# v1.net
KiCad netlist of a schematic drawn in EAGLE
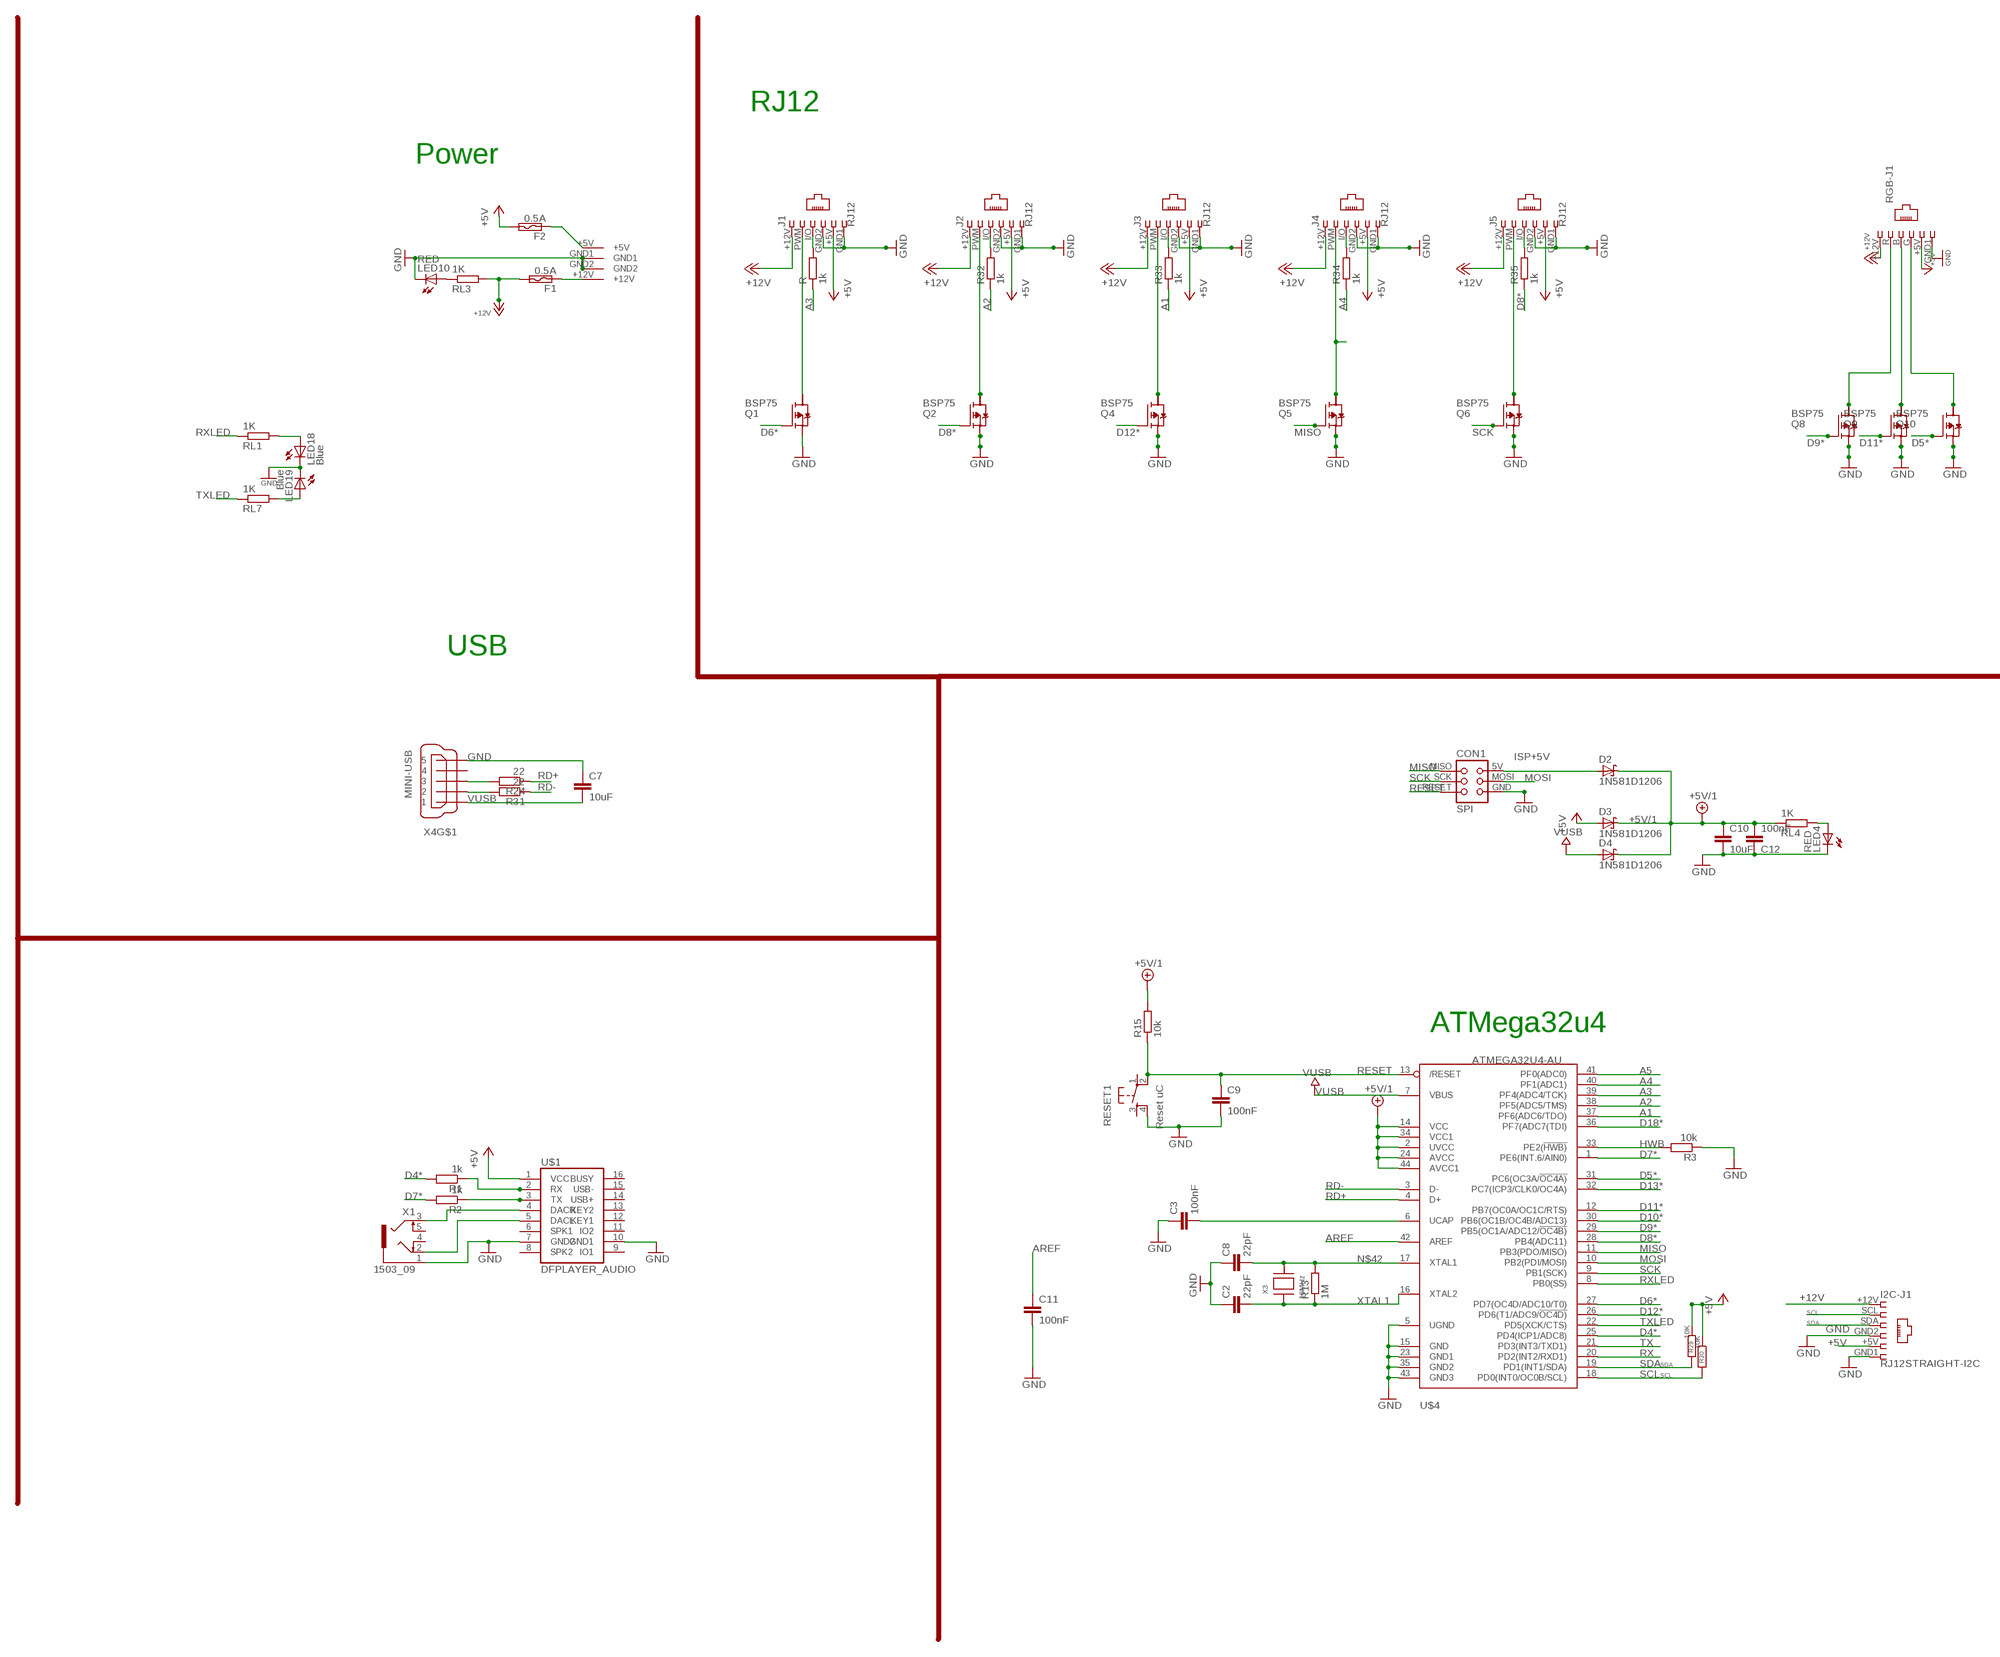
[diagram p0: schematic, sheet 1, part 1 of 2]
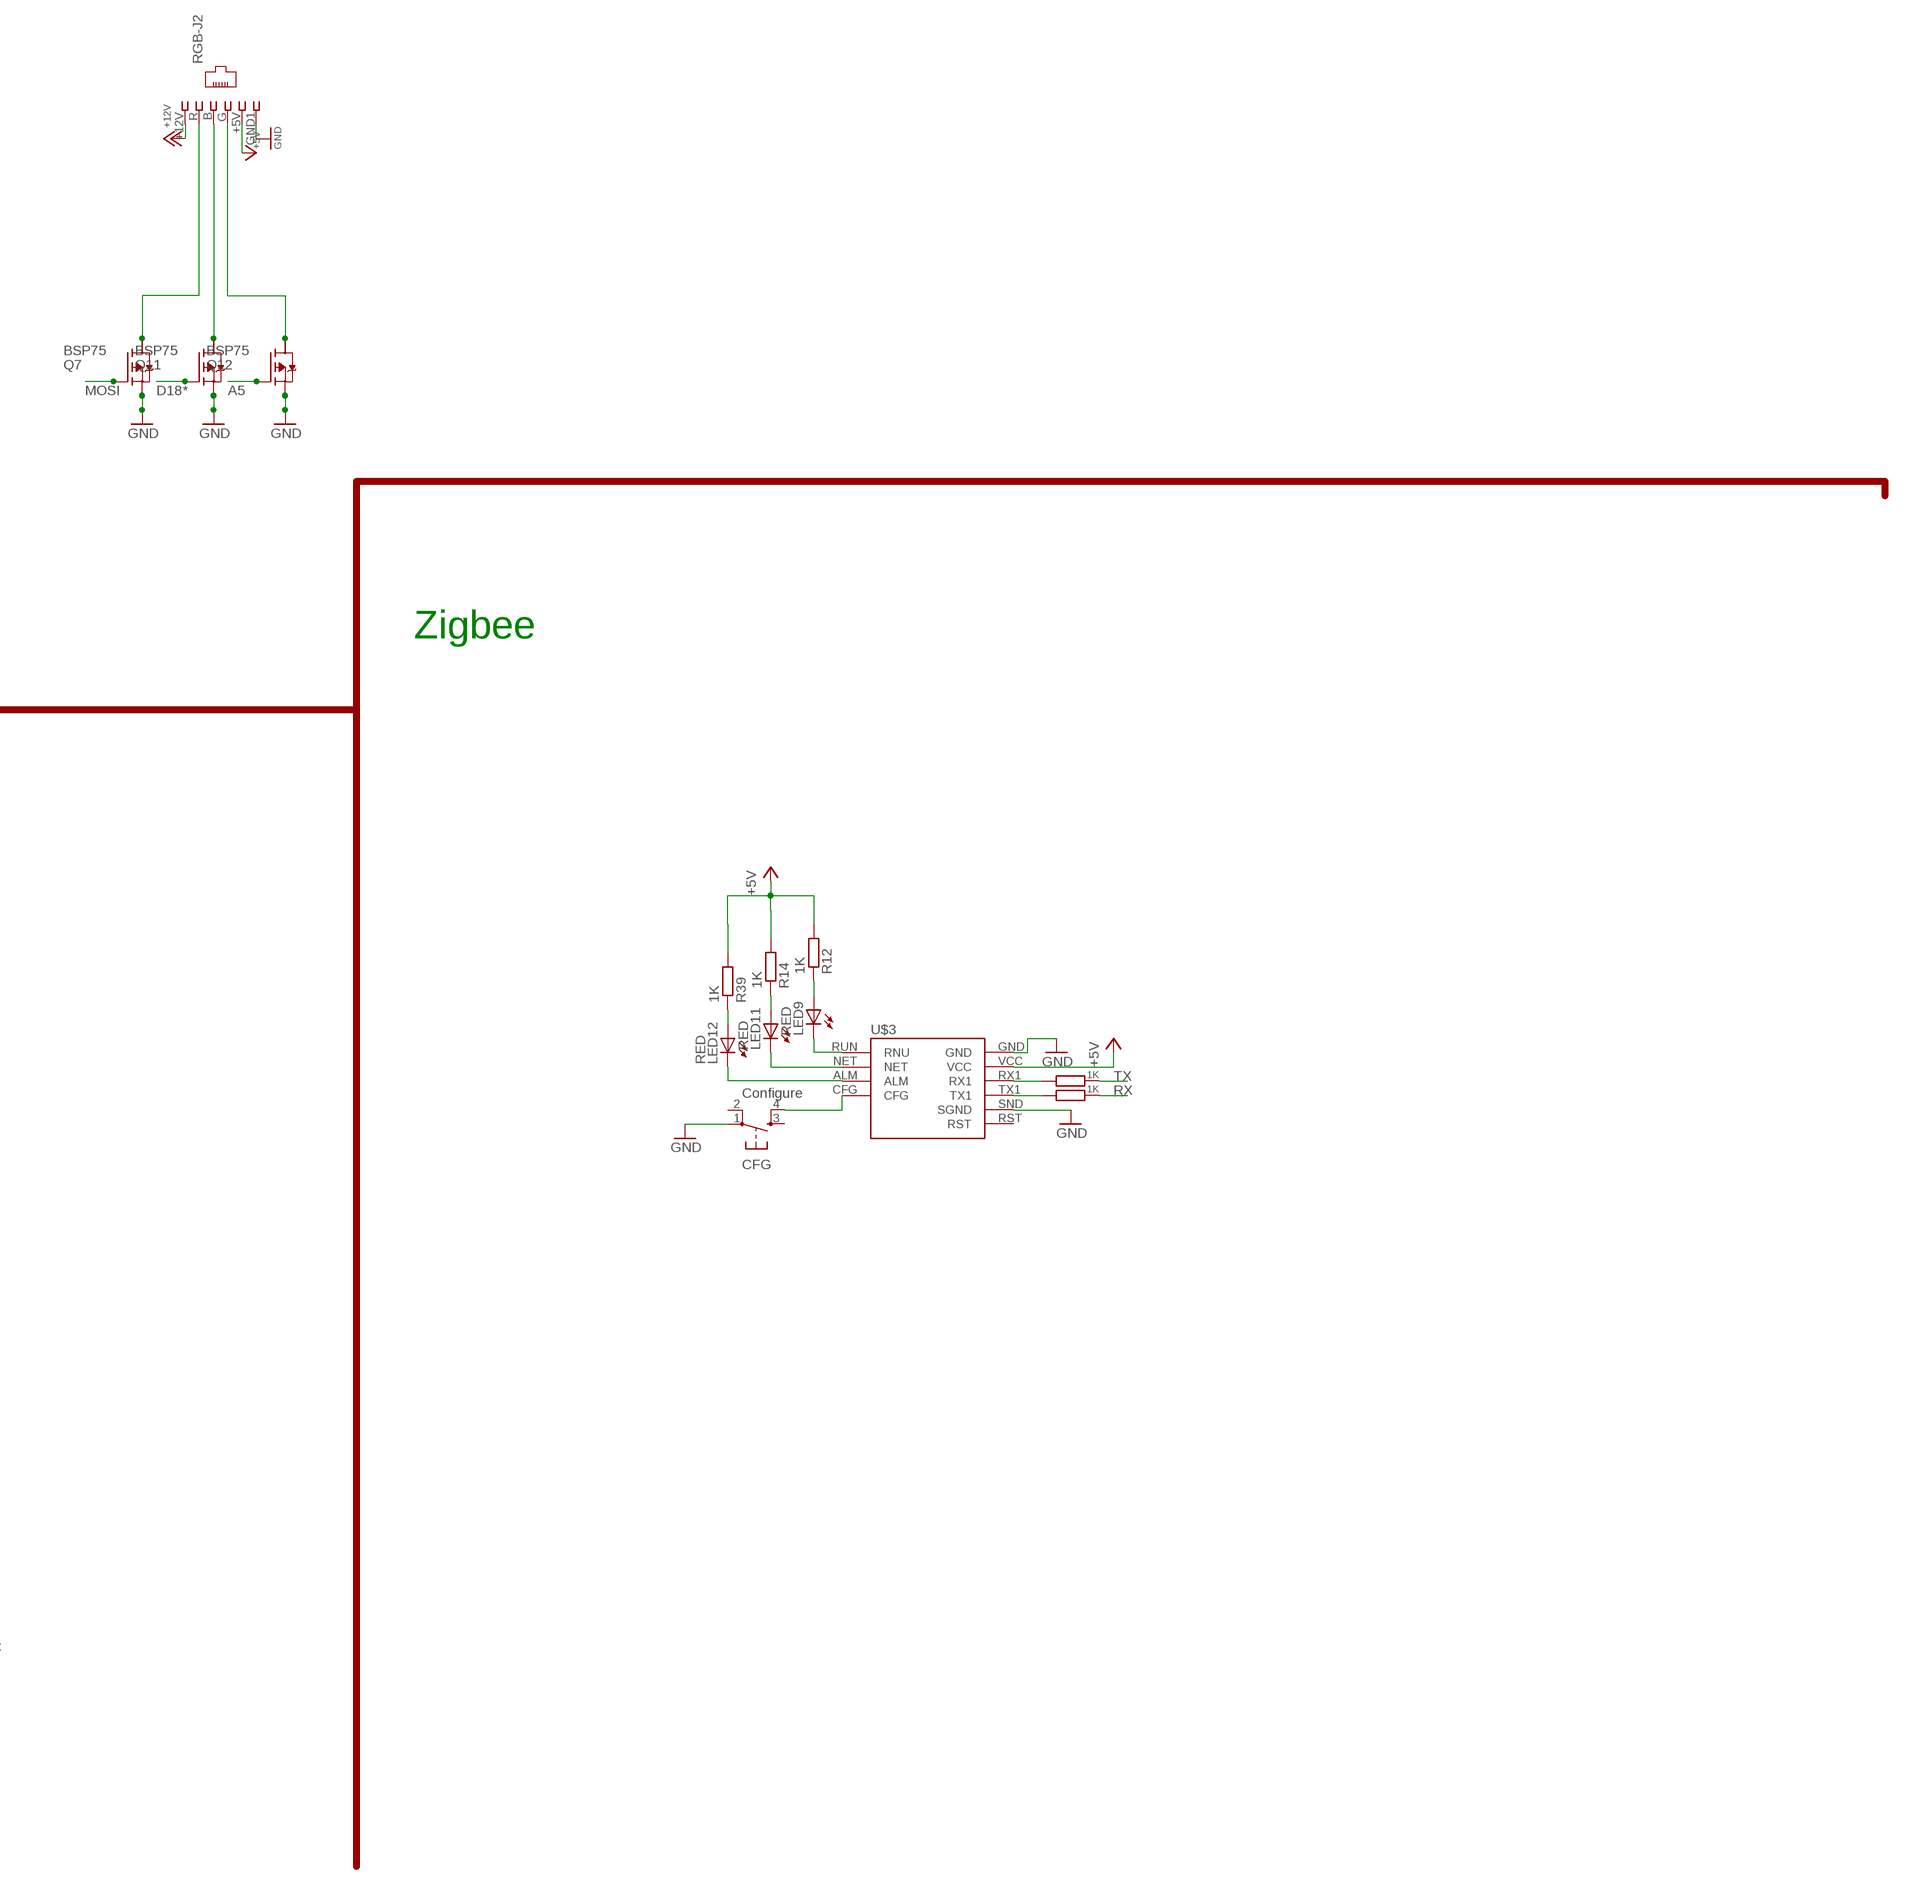
[diagram p1: schematic, sheet 1, part 2 of 2]

(export (version "E")
  (design (tool "Eeschema 10.0.6"))
  (components
    (comp (ref "C2")
      (value "22pF")
      (footprint "eagle-import:C1206")
      (libsource (lib "eagle-import") (part "C-EUC1206"))
    )
    (comp (ref "C3")
      (value "100nF")
      (footprint "eagle-import:C1206")
      (libsource (lib "eagle-import") (part "C-EUC1206"))
    )
    (comp (ref "C7")
      (value "10uF")
      (footprint "eagle-import:C1206")
      (libsource (lib "eagle-import") (part "C-EUC1206"))
    )
    (comp (ref "C8")
      (value "22pF")
      (footprint "eagle-import:C1206")
      (libsource (lib "eagle-import") (part "C-EUC1206"))
    )
    (comp (ref "C9")
      (value "100nF")
      (footprint "eagle-import:C1206")
      (libsource (lib "eagle-import") (part "C-EUC1206"))
    )
    (comp (ref "C10")
      (value "10uF")
      (footprint "eagle-import:C1206")
      (libsource (lib "eagle-import") (part "C-EUC1206"))
    )
    (comp (ref "C11")
      (value "100nF")
      (footprint "eagle-import:C1206")
      (libsource (lib "eagle-import") (part "C-EUC1206"))
    )
    (comp (ref "C12")
      (value "100nF")
      (footprint "eagle-import:C1206")
      (libsource (lib "eagle-import") (part "C-EUC1206"))
    )
    (comp (ref "CFG")
      (value "Configure")
      (footprint "eagle-import:TACTILE_SWITCH_SMD")
      (libsource (lib "eagle-import") (part "TAC_SWITCHSMD"))
    )
    (comp (ref "CON1")
      (value "SPI")
      (footprint "eagle-import:TC2030-MCP-NL")
      (libsource (lib "eagle-import") (part "TINYISPT"))
    )
    (comp (ref "D2")
      (value "1N581D1206")
      (footprint "eagle-import:LED-1206")
      (libsource (lib "eagle-import") (part "1N581D1206"))
    )
    (comp (ref "D3")
      (value "1N581D1206")
      (footprint "eagle-import:LED-1206")
      (libsource (lib "eagle-import") (part "1N581D1206"))
    )
    (comp (ref "D4")
      (value "1N581D1206")
      (footprint "eagle-import:LED-1206")
      (libsource (lib "eagle-import") (part "1N581D1206"))
    )
    (comp (ref "F1")
      (value "0.5A")
      (footprint "eagle-import:C1812")
      (libsource (lib "eagle-import") (part "POLYSWITCHSMD1812"))
    )
    (comp (ref "F2")
      (value "0.5A")
      (footprint "eagle-import:C1812")
      (libsource (lib "eagle-import") (part "POLYSWITCHSMD1812"))
    )
    (comp (ref "I2C-J1")
      (value "RJ12STRAIGHT-I2C")
      (footprint "eagle-import:RJ12-STRAIGHT-I2C")
      (libsource (lib "eagle-import") (part "RJ12STRAIGHT-I2C"))
    )
    (comp (ref "J1")
      (value "RJ12")
      (footprint "eagle-import:RJ12-STRAIGHT")
      (libsource (lib "eagle-import") (part "RJ12STRAIGHT"))
    )
    (comp (ref "J2")
      (value "RJ12")
      (footprint "eagle-import:RJ12-STRAIGHT")
      (libsource (lib "eagle-import") (part "RJ12STRAIGHT"))
    )
    (comp (ref "J3")
      (value "RJ12")
      (footprint "eagle-import:RJ12-STRAIGHT")
      (libsource (lib "eagle-import") (part "RJ12STRAIGHT"))
    )
    (comp (ref "J4")
      (value "RJ12")
      (footprint "eagle-import:RJ12-STRAIGHT")
      (libsource (lib "eagle-import") (part "RJ12STRAIGHT"))
    )
    (comp (ref "J5")
      (value "RJ12")
      (footprint "eagle-import:RJ12-STRAIGHT")
      (libsource (lib "eagle-import") (part "RJ12STRAIGHT"))
    )
    (comp (ref "LED4")
      (value "RED")
      (footprint "eagle-import:CHIPLED_1206")
      (libsource (lib "eagle-import") (part "LEDCHIPLED_1206"))
    )
    (comp (ref "LED9")
      (value "RED")
      (footprint "eagle-import:CHIP-LED0805")
      (libsource (lib "eagle-import") (part "LEDCHIP-LED0805"))
    )
    (comp (ref "LED10")
      (value "RED")
      (footprint "eagle-import:CHIPLED_1206")
      (libsource (lib "eagle-import") (part "LEDCHIPLED_1206"))
    )
    (comp (ref "LED11")
      (value "RED")
      (footprint "eagle-import:CHIP-LED0805")
      (libsource (lib "eagle-import") (part "LEDCHIP-LED0805"))
    )
    (comp (ref "LED12")
      (value "RED")
      (footprint "eagle-import:CHIP-LED0805")
      (libsource (lib "eagle-import") (part "LEDCHIP-LED0805"))
    )
    (comp (ref "LED18")
      (value "Blue")
      (footprint "eagle-import:CHIPLED_1206")
      (libsource (lib "eagle-import") (part "LEDCHIPLED_1206"))
    )
    (comp (ref "LED19")
      (value "Blue")
      (footprint "eagle-import:CHIPLED_1206")
      (libsource (lib "eagle-import") (part "LEDCHIPLED_1206"))
    )
    (comp (ref "Q1")
      (value "BSP75")
      (footprint "eagle-import:PG-SOT-223")
      (libsource (lib "eagle-import") (part "BSP613P"))
    )
    (comp (ref "Q2")
      (value "BSP75")
      (footprint "eagle-import:PG-SOT-223")
      (libsource (lib "eagle-import") (part "BSP613P"))
    )
    (comp (ref "Q4")
      (value "BSP75")
      (footprint "eagle-import:PG-SOT-223")
      (libsource (lib "eagle-import") (part "BSP613P"))
    )
    (comp (ref "Q5")
      (value "BSP75")
      (footprint "eagle-import:PG-SOT-223")
      (libsource (lib "eagle-import") (part "BSP613P"))
    )
    (comp (ref "Q6")
      (value "BSP75")
      (footprint "eagle-import:PG-SOT-223")
      (libsource (lib "eagle-import") (part "BSP613P"))
    )
    (comp (ref "Q7")
      (value "BSP75")
      (footprint "eagle-import:PG-SOT-223")
      (libsource (lib "eagle-import") (part "BSP613P"))
    )
    (comp (ref "Q8")
      (value "BSP75")
      (footprint "eagle-import:PG-SOT-223")
      (libsource (lib "eagle-import") (part "BSP613P"))
    )
    (comp (ref "Q9")
      (value "BSP75")
      (footprint "eagle-import:PG-SOT-223")
      (libsource (lib "eagle-import") (part "BSP613P"))
    )
    (comp (ref "Q10")
      (value "BSP75")
      (footprint "eagle-import:PG-SOT-223")
      (libsource (lib "eagle-import") (part "BSP613P"))
    )
    (comp (ref "Q11")
      (value "BSP75")
      (footprint "eagle-import:PG-SOT-223")
      (libsource (lib "eagle-import") (part "BSP613P"))
    )
    (comp (ref "Q12")
      (value "BSP75")
      (footprint "eagle-import:PG-SOT-223")
      (libsource (lib "eagle-import") (part "BSP613P"))
    )
    (comp (ref "R")
      (value "1k")
      (footprint "eagle-import:R0805")
      (libsource (lib "eagle-import") (part "R-EU_R0805"))
    )
    (comp (ref "R1")
      (value "1k")
      (footprint "eagle-import:R0805")
      (libsource (lib "eagle-import") (part "R-EU_R0805"))
    )
    (comp (ref "R2")
      (value "1k")
      (footprint "eagle-import:R0805")
      (libsource (lib "eagle-import") (part "R-EU_R0805"))
    )
    (comp (ref "R3")
      (value "10k")
      (footprint "eagle-import:M0805")
      (libsource (lib "eagle-import") (part "resistor_R-EU_M0805"))
    )
    (comp (ref "R8")
      (value "1K")
      (footprint "eagle-import:R0805")
      (libsource (lib "eagle-import") (part "R-EU_R0805"))
    )
    (comp (ref "R11")
      (value "1K")
      (footprint "eagle-import:R0805")
      (libsource (lib "eagle-import") (part "R-EU_R0805"))
    )
    (comp (ref "R12")
      (value "1K")
      (footprint "eagle-import:R0805")
      (libsource (lib "eagle-import") (part "R-EU_R0805"))
    )
    (comp (ref "R13")
      (value "1M")
      (footprint "eagle-import:R1206")
      (libsource (lib "eagle-import") (part "R-EU_R1206"))
    )
    (comp (ref "R14")
      (value "1K")
      (footprint "eagle-import:R0805")
      (libsource (lib "eagle-import") (part "R-EU_R0805"))
    )
    (comp (ref "R15")
      (value "10k")
      (footprint "eagle-import:M0805")
      (libsource (lib "eagle-import") (part "resistor_R-EU_M0805"))
    )
    (comp (ref "R24")
      (value "22")
      (footprint "eagle-import:M1206")
      (libsource (lib "eagle-import") (part "resistor_R-EU_M1206"))
    )
    (comp (ref "R29")
      (value "10K")
      (footprint "eagle-import:M0805")
      (libsource (lib "eagle-import") (part "resistor_R-EU_M0805"))
    )
    (comp (ref "R30")
      (value "10K")
      (footprint "eagle-import:M0805")
      (libsource (lib "eagle-import") (part "resistor_R-EU_M0805"))
    )
    (comp (ref "R31")
      (value "22")
      (footprint "eagle-import:M1206")
      (libsource (lib "eagle-import") (part "resistor_R-EU_M1206"))
    )
    (comp (ref "R32")
      (value "1k")
      (footprint "eagle-import:R0805")
      (libsource (lib "eagle-import") (part "R-EU_R0805"))
    )
    (comp (ref "R33")
      (value "1k")
      (footprint "eagle-import:R0805")
      (libsource (lib "eagle-import") (part "R-EU_R0805"))
    )
    (comp (ref "R34")
      (value "1k")
      (footprint "eagle-import:R0805")
      (libsource (lib "eagle-import") (part "R-EU_R0805"))
    )
    (comp (ref "R35")
      (value "1k")
      (footprint "eagle-import:R0805")
      (libsource (lib "eagle-import") (part "R-EU_R0805"))
    )
    (comp (ref "R39")
      (value "1K")
      (footprint "eagle-import:R0805")
      (libsource (lib "eagle-import") (part "R-EU_R0805"))
    )
    (comp (ref "RESET1")
      (value "Reset uC")
      (footprint "eagle-import:TACTILE_SWITCH_SMD")
      (libsource (lib "eagle-import") (part "TAC_SWITCHSMD"))
    )
    (comp (ref "RGB-J1")
      (value "RJ12")
      (footprint "eagle-import:RJ12-STRAIGHT-RGB")
      (libsource (lib "eagle-import") (part "RJ12STRAIGHT-RGB"))
    )
    (comp (ref "RGB-J2")
      (value "RJ12")
      (footprint "eagle-import:RJ12-STRAIGHT-RGB")
      (libsource (lib "eagle-import") (part "RJ12STRAIGHT-RGB"))
    )
    (comp (ref "RL1")
      (value "1K")
      (footprint "eagle-import:R0805")
      (libsource (lib "eagle-import") (part "R-EU_R0805"))
    )
    (comp (ref "RL3")
      (value "1K")
      (footprint "eagle-import:R0805")
      (libsource (lib "eagle-import") (part "R-EU_R0805"))
    )
    (comp (ref "RL4")
      (value "1K")
      (footprint "eagle-import:R0805")
      (libsource (lib "eagle-import") (part "resistor_R-EU_R0805"))
    )
    (comp (ref "RL7")
      (value "1K")
      (footprint "eagle-import:R0805")
      (libsource (lib "eagle-import") (part "R-EU_R0805"))
    )
    (comp (ref "U$1")
      (value "DFPLAYER_AUDIO")
      (footprint "eagle-import:DIL16-7")
      (libsource (lib "eagle-import") (part "DFPLAYER_AUDIO"))
    )
    (comp (ref "U$3")
      (value "SZ05-ZIGBEESMD")
      (footprint "eagle-import:SZ05-ZIGBEE3")
      (libsource (lib "eagle-import") (part "SZ05-ZIGBEESMD"))
    )
    (comp (ref "U$4")
      (value "ATMEGA32U4-AU")
      (footprint "eagle-import:TQFP44")
      (libsource (lib "eagle-import") (part "ATMEGA32U4-AU"))
    )
    (comp (ref "U$6")
      (value "KPJX-4S-S")
      (footprint "eagle-import:KPJX-4S-S")
      (libsource (lib "eagle-import") (part "KPJX-4S-S"))
    )
    (comp (ref "X1")
      (value "1503_09")
      (footprint "eagle-import:1503_09")
      (libsource (lib "eagle-import") (part "1503_09"))
    )
    (comp (ref "X3")
      (value "16MHz")
      (footprint "eagle-import:NX6035")
      (libsource (lib "eagle-import") (part "XTALNX6035"))
    )
    (comp (ref "X4")
      (value "MINI-USB")
      (footprint "eagle-import:32005-201")
      (libsource (lib "eagle-import") (part "MINI-USB-SCHIELD-32005-201"))
    )
  )
  (nets
    (net (code "1") (name "+5V") (class "Default")
      (node (ref "D3") (pin "A") (pinfunction "A_A") (pintype "passive"))
      (node (ref "F2") (pin "2") (pinfunction "2_2") (pintype "passive"))
      (node (ref "I2C-J1") (pin "+5V") (pinfunction "5_+5V") (pintype "bidirectional"))
      (node (ref "J1") (pin "+5V") (pinfunction "5_+5V") (pintype "bidirectional"))
      (node (ref "J2") (pin "+5V") (pinfunction "5_+5V") (pintype "bidirectional"))
      (node (ref "J3") (pin "+5V") (pinfunction "5_+5V") (pintype "bidirectional"))
      (node (ref "J4") (pin "+5V") (pinfunction "5_+5V") (pintype "bidirectional"))
      (node (ref "J5") (pin "+5V") (pinfunction "5_+5V") (pintype "bidirectional"))
      (node (ref "R12") (pin "2") (pinfunction "2_2") (pintype "passive"))
      (node (ref "R14") (pin "2") (pinfunction "2_2") (pintype "passive"))
      (node (ref "R29") (pin "1") (pinfunction "1_1") (pintype "passive"))
      (node (ref "R30") (pin "1") (pinfunction "1_1") (pintype "passive"))
      (node (ref "R39") (pin "2") (pinfunction "2_2") (pintype "passive"))
      (node (ref "RGB-J1") (pin "+5V") (pinfunction "5_+5V") (pintype "bidirectional"))
      (node (ref "RGB-J2") (pin "+5V") (pinfunction "5_+5V") (pintype "bidirectional"))
      (node (ref "U$1") (pin "1") (pinfunction "VCC_1") (pintype "power_in"))
      (node (ref "U$3") (pin "VCC") (pinfunction "VCC_VCC") (pintype "bidirectional"))
    )
    (net (code "2") (name "+5V{slash}1") (class "Default")
      (node (ref "C10") (pin "1") (pinfunction "1_1") (pintype "passive"))
      (node (ref "C12") (pin "2") (pinfunction "2_2") (pintype "passive"))
      (node (ref "D2") (pin "C") (pinfunction "C_C") (pintype "passive"))
      (node (ref "D3") (pin "C") (pinfunction "C_C") (pintype "passive"))
      (node (ref "D4") (pin "C") (pinfunction "C_C") (pintype "passive"))
      (node (ref "R15") (pin "2") (pinfunction "2_2") (pintype "passive"))
      (node (ref "RL4") (pin "1") (pinfunction "1_1") (pintype "passive"))
      (node (ref "U$4") (pin "14") (pinfunction "VCC_14") (pintype "bidirectional"))
      (node (ref "U$4") (pin "2") (pinfunction "UVCC_2") (pintype "bidirectional"))
      (node (ref "U$4") (pin "24") (pinfunction "AVCC_24") (pintype "bidirectional"))
      (node (ref "U$4") (pin "34") (pinfunction "VCC1_34") (pintype "bidirectional"))
      (node (ref "U$4") (pin "44") (pinfunction "AVCC1_44") (pintype "bidirectional"))
    )
    (net (code "3") (name "+12V") (class "Default")
      (node (ref "F1") (pin "2") (pinfunction "2_2") (pintype "passive"))
      (node (ref "I2C-J1") (pin "+12V") (pinfunction "1_+12V") (pintype "bidirectional"))
      (node (ref "J1") (pin "+12V") (pinfunction "1_+12V") (pintype "bidirectional"))
      (node (ref "J2") (pin "+12V") (pinfunction "1_+12V") (pintype "bidirectional"))
      (node (ref "J3") (pin "+12V") (pinfunction "1_+12V") (pintype "bidirectional"))
      (node (ref "J4") (pin "+12V") (pinfunction "1_+12V") (pintype "bidirectional"))
      (node (ref "J5") (pin "+12V") (pinfunction "1_+12V") (pintype "bidirectional"))
      (node (ref "RGB-J1") (pin "+12V") (pinfunction "1_+12V") (pintype "bidirectional"))
      (node (ref "RGB-J2") (pin "+12V") (pinfunction "1_+12V") (pintype "bidirectional"))
      (node (ref "RL3") (pin "2") (pinfunction "2_2") (pintype "passive"))
    )
    (net (code "4") (name "/A1") (class "Default")
      (node (ref "R33") (pin "1") (pinfunction "1_1") (pintype "passive"))
      (node (ref "U$4") (pin "37") (pinfunction "PF6(ADC6/TDO)_37") (pintype "bidirectional"))
    )
    (net (code "5") (name "/A2") (class "Default")
      (node (ref "R32") (pin "1") (pinfunction "1_1") (pintype "passive"))
      (node (ref "U$4") (pin "38") (pinfunction "PF5(ADC5/TMS)_38") (pintype "bidirectional"))
    )
    (net (code "6") (name "/A3") (class "Default")
      (node (ref "R") (pin "1") (pinfunction "1_1") (pintype "passive"))
      (node (ref "U$4") (pin "39") (pinfunction "PF4(ADC4/TCK)_39") (pintype "bidirectional"))
    )
    (net (code "7") (name "/A4") (class "Default")
      (node (ref "R34") (pin "1") (pinfunction "1_1") (pintype "passive"))
      (node (ref "U$4") (pin "40") (pinfunction "PF1(ADC1)_40") (pintype "bidirectional"))
    )
    (net (code "8") (name "/A5") (class "Default")
      (node (ref "Q12") (pin "1") (pinfunction "G_1") (pintype "passive"))
      (node (ref "U$4") (pin "41") (pinfunction "PF0(ADC0)_41") (pintype "bidirectional"))
    )
    (net (code "9") (name "/AREF") (class "Default")
      (node (ref "C11") (pin "1") (pinfunction "1_1") (pintype "passive"))
      (node (ref "U$4") (pin "42") (pinfunction "AREF_42") (pintype "bidirectional"))
    )
    (net (code "10") (name "/D4*") (class "Default")
      (node (ref "R1") (pin "2") (pinfunction "2_2") (pintype "passive"))
      (node (ref "U$4") (pin "25") (pinfunction "PD4(ICP1/ADC8)_25") (pintype "bidirectional"))
    )
    (net (code "11") (name "/D5*") (class "Default")
      (node (ref "Q10") (pin "1") (pinfunction "G_1") (pintype "passive"))
      (node (ref "U$4") (pin "31") (pinfunction "PC6(OC3A/~{OC4A})_31") (pintype "bidirectional"))
    )
    (net (code "12") (name "/D6*") (class "Default")
      (node (ref "Q1") (pin "1") (pinfunction "G_1") (pintype "passive"))
      (node (ref "U$4") (pin "27") (pinfunction "PD7(OC4D/ADC10/T0)_27") (pintype "bidirectional"))
    )
    (net (code "13") (name "/D7*") (class "Default")
      (node (ref "R2") (pin "2") (pinfunction "2_2") (pintype "passive"))
      (node (ref "U$4") (pin "1") (pinfunction "PE6(INT.6/AIN0)_1") (pintype "bidirectional"))
    )
    (net (code "14") (name "/D8*") (class "Default")
      (node (ref "Q2") (pin "1") (pinfunction "G_1") (pintype "passive"))
      (node (ref "R35") (pin "1") (pinfunction "1_1") (pintype "passive"))
      (node (ref "U$4") (pin "28") (pinfunction "PB4(ADC11)_28") (pintype "bidirectional"))
    )
    (net (code "15") (name "/D9*") (class "Default")
      (node (ref "Q8") (pin "1") (pinfunction "G_1") (pintype "passive"))
      (node (ref "U$4") (pin "29") (pinfunction "PB5(OC1A/ADC12/~{OC4B})_29") (pintype "bidirectional"))
    )
    (net (code "16") (name "/D10*") (class "Default")
      (node (ref "U$4") (pin "30") (pinfunction "PB6(OC1B/OC4B/ADC13)_30") (pintype "bidirectional"))
    )
    (net (code "17") (name "/D11*") (class "Default")
      (node (ref "Q9") (pin "1") (pinfunction "G_1") (pintype "passive"))
      (node (ref "U$4") (pin "12") (pinfunction "PB7(OC0A/OC1C/RTS)_12") (pintype "bidirectional"))
    )
    (net (code "18") (name "/D12*") (class "Default")
      (node (ref "Q4") (pin "1") (pinfunction "G_1") (pintype "passive"))
      (node (ref "U$4") (pin "26") (pinfunction "PD6(T1/ADC9/~{OC4D})_26") (pintype "bidirectional"))
    )
    (net (code "19") (name "/D13*") (class "Default")
      (node (ref "U$4") (pin "32") (pinfunction "PC7(ICP3/CLK0/OC4A)_32") (pintype "bidirectional"))
    )
    (net (code "20") (name "/D18*") (class "Default")
      (node (ref "Q11") (pin "1") (pinfunction "G_1") (pintype "passive"))
      (node (ref "U$4") (pin "36") (pinfunction "PF7(ADC7(TDI)_36") (pintype "bidirectional"))
    )
    (net (code "21") (name "/HWB") (class "Default")
      (node (ref "R3") (pin "2") (pinfunction "2_2") (pintype "passive"))
      (node (ref "U$4") (pin "33") (pinfunction "PE2(~{HWB})_33") (pintype "bidirectional"))
    )
    (net (code "22") (name "/ISP+5V") (class "Default")
      (node (ref "CON1") (pin "5V") (pinfunction "VCC_5V") (pintype "passive"))
      (node (ref "D2") (pin "A") (pinfunction "A_A") (pintype "passive"))
    )
    (net (code "23") (name "/MISO") (class "Default")
      (node (ref "CON1") (pin "MISO") (pinfunction "MISO_MISO") (pintype "passive"))
      (node (ref "Q5") (pin "1") (pinfunction "G_1") (pintype "passive"))
      (node (ref "U$4") (pin "11") (pinfunction "PB3(PDO/MISO)_11") (pintype "bidirectional"))
    )
    (net (code "24") (name "/MOSI") (class "Default")
      (node (ref "CON1") (pin "MOSI") (pinfunction "MOSI_MOSI") (pintype "passive"))
      (node (ref "Q7") (pin "1") (pinfunction "G_1") (pintype "passive"))
      (node (ref "U$4") (pin "10") (pinfunction "PB2(PDI/MOSI)_10") (pintype "bidirectional"))
    )
    (net (code "25") (name "/N$42") (class "Default")
      (node (ref "C8") (pin "2") (pinfunction "2_2") (pintype "passive"))
      (node (ref "R13") (pin "2") (pinfunction "2_2") (pintype "passive"))
      (node (ref "U$4") (pin "17") (pinfunction "XTAL1_17") (pintype "bidirectional"))
      (node (ref "X3") (pin "P$2") (pinfunction "P$2_P$2") (pintype "bidirectional"))
    )
    (net (code "26") (name "/RD+") (class "Default")
      (node (ref "R24") (pin "1") (pinfunction "1_1") (pintype "passive"))
      (node (ref "U$4") (pin "4") (pinfunction "D+_4") (pintype "bidirectional"))
    )
    (net (code "27") (name "/RD-") (class "Default")
      (node (ref "R31") (pin "1") (pinfunction "1_1") (pintype "passive"))
      (node (ref "U$4") (pin "3") (pinfunction "D-_3") (pintype "bidirectional"))
    )
    (net (code "28") (name "/RESET") (class "Default")
      (node (ref "C9") (pin "1") (pinfunction "1_1") (pintype "passive"))
      (node (ref "CON1") (pin "RESET") (pinfunction "RESET_RESET") (pintype "passive"))
      (node (ref "R15") (pin "1") (pinfunction "1_1") (pintype "passive"))
      (node (ref "RESET1") (pin "2") (pinfunction "2_2") (pintype "passive"))
      (node (ref "U$4") (pin "13") (pinfunction "/RESET_13") (pintype "bidirectional"))
    )
    (net (code "29") (name "/RX") (class "Default")
      (node (ref "R8") (pin "1") (pinfunction "1_1") (pintype "passive"))
      (node (ref "U$4") (pin "20") (pinfunction "PD2(INT2/RXD1)_20") (pintype "bidirectional"))
    )
    (net (code "30") (name "/RXLED") (class "Default")
      (node (ref "RL1") (pin "1") (pinfunction "1_1") (pintype "passive"))
      (node (ref "U$4") (pin "8") (pinfunction "PB0(SS)_8") (pintype "bidirectional"))
    )
    (net (code "31") (name "/SCK") (class "Default")
      (node (ref "CON1") (pin "SCK") (pinfunction "SCK_SCK") (pintype "passive"))
      (node (ref "Q6") (pin "1") (pinfunction "G_1") (pintype "passive"))
      (node (ref "U$4") (pin "9") (pinfunction "PB1(SCK)_9") (pintype "bidirectional"))
    )
    (net (code "32") (name "/SCL") (class "Default")
      (node (ref "I2C-J1") (pin "SCL") (pinfunction "2_SCL") (pintype "bidirectional"))
      (node (ref "R30") (pin "2") (pinfunction "2_2") (pintype "passive"))
      (node (ref "U$4") (pin "18") (pinfunction "PD0(INT0/OC0B/SCL)_18") (pintype "bidirectional"))
    )
    (net (code "33") (name "/SDA") (class "Default")
      (node (ref "I2C-J1") (pin "SDA") (pinfunction "3_SDA") (pintype "bidirectional"))
      (node (ref "R29") (pin "2") (pinfunction "2_2") (pintype "passive"))
      (node (ref "U$4") (pin "19") (pinfunction "PD1(INT1/SDA)_19") (pintype "bidirectional"))
    )
    (net (code "34") (name "/TX") (class "Default")
      (node (ref "R11") (pin "1") (pinfunction "1_1") (pintype "passive"))
      (node (ref "U$4") (pin "21") (pinfunction "PD3(INT3/TXD1)_21") (pintype "bidirectional"))
    )
    (net (code "35") (name "/TXLED") (class "Default")
      (node (ref "RL7") (pin "1") (pinfunction "1_1") (pintype "passive"))
      (node (ref "U$4") (pin "22") (pinfunction "PD5(XCK/CTS)_22") (pintype "bidirectional"))
    )
    (net (code "36") (name "/XTAL1") (class "Default")
      (node (ref "C2") (pin "2") (pinfunction "2_2") (pintype "passive"))
      (node (ref "R13") (pin "1") (pinfunction "1_1") (pintype "passive"))
      (node (ref "U$4") (pin "16") (pinfunction "XTAL2_16") (pintype "bidirectional"))
      (node (ref "X3") (pin "P$1") (pinfunction "P$1_P$1") (pintype "bidirectional"))
    )
    (net (code "37") (name "GND") (class "Default")
      (node (ref "C10") (pin "2") (pinfunction "2_2") (pintype "passive"))
      (node (ref "C11") (pin "2") (pinfunction "2_2") (pintype "passive"))
      (node (ref "C12") (pin "1") (pinfunction "1_1") (pintype "passive"))
      (node (ref "C2") (pin "1") (pinfunction "1_1") (pintype "passive"))
      (node (ref "C3") (pin "1") (pinfunction "1_1") (pintype "passive"))
      (node (ref "C7") (pin "1") (pinfunction "1_1") (pintype "passive"))
      (node (ref "C8") (pin "1") (pinfunction "1_1") (pintype "passive"))
      (node (ref "C9") (pin "2") (pinfunction "2_2") (pintype "passive"))
      (node (ref "CFG") (pin "1") (pinfunction "1_1") (pintype "passive"))
      (node (ref "CON1") (pin "GND") (pinfunction "GND_GND") (pintype "passive"))
      (node (ref "I2C-J1") (pin "GND1") (pinfunction "6_GND1") (pintype "bidirectional"))
      (node (ref "I2C-J1") (pin "GND2") (pinfunction "4_GND2") (pintype "bidirectional"))
      (node (ref "J1") (pin "GND1") (pinfunction "6_GND1") (pintype "bidirectional"))
      (node (ref "J1") (pin "GND2") (pinfunction "4_GND2") (pintype "bidirectional"))
      (node (ref "J2") (pin "GND1") (pinfunction "6_GND1") (pintype "bidirectional"))
      (node (ref "J2") (pin "GND2") (pinfunction "4_GND2") (pintype "bidirectional"))
      (node (ref "J3") (pin "GND1") (pinfunction "6_GND1") (pintype "bidirectional"))
      (node (ref "J3") (pin "GND2") (pinfunction "4_GND2") (pintype "bidirectional"))
      (node (ref "J4") (pin "GND1") (pinfunction "6_GND1") (pintype "bidirectional"))
      (node (ref "J4") (pin "GND2") (pinfunction "4_GND2") (pintype "bidirectional"))
      (node (ref "J5") (pin "GND1") (pinfunction "6_GND1") (pintype "bidirectional"))
      (node (ref "J5") (pin "GND2") (pinfunction "4_GND2") (pintype "bidirectional"))
      (node (ref "LED10") (pin "C") (pinfunction "C_C") (pintype "passive"))
      (node (ref "LED18") (pin "C") (pinfunction "C_C") (pintype "passive"))
      (node (ref "LED19") (pin "C") (pinfunction "C_C") (pintype "passive"))
      (node (ref "LED4") (pin "C") (pinfunction "C_C") (pintype "passive"))
      (node (ref "Q1") (pin "3") (pinfunction "S_3") (pintype "passive"))
      (node (ref "Q10") (pin "3") (pinfunction "S_3") (pintype "passive"))
      (node (ref "Q11") (pin "3") (pinfunction "S_3") (pintype "passive"))
      (node (ref "Q12") (pin "3") (pinfunction "S_3") (pintype "passive"))
      (node (ref "Q2") (pin "3") (pinfunction "S_3") (pintype "passive"))
      (node (ref "Q4") (pin "3") (pinfunction "S_3") (pintype "passive"))
      (node (ref "Q5") (pin "3") (pinfunction "S_3") (pintype "passive"))
      (node (ref "Q6") (pin "3") (pinfunction "S_3") (pintype "passive"))
      (node (ref "Q7") (pin "3") (pinfunction "S_3") (pintype "passive"))
      (node (ref "Q8") (pin "3") (pinfunction "S_3") (pintype "passive"))
      (node (ref "Q9") (pin "3") (pinfunction "S_3") (pintype "passive"))
      (node (ref "R3") (pin "1") (pinfunction "1_1") (pintype "passive"))
      (node (ref "RESET1") (pin "4") (pinfunction "4_4") (pintype "passive"))
      (node (ref "RGB-J1") (pin "GND1") (pinfunction "6_GND1") (pintype "bidirectional"))
      (node (ref "RGB-J2") (pin "GND1") (pinfunction "6_GND1") (pintype "bidirectional"))
      (node (ref "U$1") (pin "10") (pinfunction "GND1_10") (pintype "power_in"))
      (node (ref "U$1") (pin "7") (pinfunction "GND2_7") (pintype "power_in"))
      (node (ref "U$3") (pin "GND") (pinfunction "GND_GND") (pintype "bidirectional"))
      (node (ref "U$3") (pin "SND") (pinfunction "SGND_SND") (pintype "bidirectional"))
      (node (ref "U$4") (pin "15") (pinfunction "GND_15") (pintype "bidirectional"))
      (node (ref "U$4") (pin "23") (pinfunction "GND1_23") (pintype "bidirectional"))
      (node (ref "U$4") (pin "35") (pinfunction "GND2_35") (pintype "bidirectional"))
      (node (ref "U$4") (pin "43") (pinfunction "GND3_43") (pintype "bidirectional"))
      (node (ref "U$4") (pin "5") (pinfunction "UGND_5") (pintype "bidirectional"))
      (node (ref "U$6") (pin "GND1") (pinfunction "GND1_GND1") (pintype "input"))
      (node (ref "U$6") (pin "GND2") (pinfunction "GND2_GND2") (pintype "input"))
      (node (ref "X1") (pin "1") (pinfunction "1_1") (pintype "passive"))
      (node (ref "X4") (pin "5") (pinfunction "5_5") (pintype "passive"))
    )
    (net (code "38") (name "Net-(CFG-Pad4)") (class "Default")
      (node (ref "CFG") (pin "4") (pinfunction "4_4") (pintype "passive"))
      (node (ref "U$3") (pin "CFG") (pinfunction "CFG_CFG") (pintype "bidirectional"))
    )
    (net (code "39") (name "Net-(F1-Pad1)") (class "Default")
      (node (ref "F1") (pin "1") (pinfunction "1_1") (pintype "passive"))
      (node (ref "U$6") (pin "+12V") (pinfunction "+12V_+12V") (pintype "power_in"))
    )
    (net (code "40") (name "Net-(F2-Pad1)") (class "Default")
      (node (ref "F2") (pin "1") (pinfunction "1_1") (pintype "passive"))
      (node (ref "U$6") (pin "+5V") (pinfunction "+5V_+5V") (pintype "power_in"))
    )
    (net (code "41") (name "Net-(J1-2)") (class "Default")
      (node (ref "J1") (pin "PWM") (pinfunction "2_PWM") (pintype "bidirectional"))
      (node (ref "Q1") (pin "2") (pinfunction "D_2") (pintype "passive"))
    )
    (net (code "42") (name "Net-(J1-3)") (class "Default")
      (node (ref "J1") (pin "I/O") (pinfunction "3_I/O") (pintype "bidirectional"))
      (node (ref "R") (pin "2") (pinfunction "2_2") (pintype "passive"))
    )
    (net (code "43") (name "Net-(J2-2)") (class "Default")
      (node (ref "J2") (pin "PWM") (pinfunction "2_PWM") (pintype "bidirectional"))
      (node (ref "Q2") (pin "2") (pinfunction "D_2") (pintype "passive"))
    )
    (net (code "44") (name "Net-(J2-3)") (class "Default")
      (node (ref "J2") (pin "I/O") (pinfunction "3_I/O") (pintype "bidirectional"))
      (node (ref "R32") (pin "2") (pinfunction "2_2") (pintype "passive"))
    )
    (net (code "45") (name "Net-(J3-2)") (class "Default")
      (node (ref "J3") (pin "PWM") (pinfunction "2_PWM") (pintype "bidirectional"))
      (node (ref "Q4") (pin "2") (pinfunction "D_2") (pintype "passive"))
    )
    (net (code "46") (name "Net-(J3-3)") (class "Default")
      (node (ref "J3") (pin "I/O") (pinfunction "3_I/O") (pintype "bidirectional"))
      (node (ref "R33") (pin "2") (pinfunction "2_2") (pintype "passive"))
    )
    (net (code "47") (name "Net-(J4-2)") (class "Default")
      (node (ref "J4") (pin "PWM") (pinfunction "2_PWM") (pintype "bidirectional"))
      (node (ref "Q5") (pin "2") (pinfunction "D_2") (pintype "passive"))
    )
    (net (code "48") (name "Net-(J4-3)") (class "Default")
      (node (ref "J4") (pin "I/O") (pinfunction "3_I/O") (pintype "bidirectional"))
      (node (ref "R34") (pin "2") (pinfunction "2_2") (pintype "passive"))
    )
    (net (code "49") (name "Net-(J5-2)") (class "Default")
      (node (ref "J5") (pin "PWM") (pinfunction "2_PWM") (pintype "bidirectional"))
      (node (ref "Q6") (pin "2") (pinfunction "D_2") (pintype "passive"))
    )
    (net (code "50") (name "Net-(J5-3)") (class "Default")
      (node (ref "J5") (pin "I/O") (pinfunction "3_I/O") (pintype "bidirectional"))
      (node (ref "R35") (pin "2") (pinfunction "2_2") (pintype "passive"))
    )
    (net (code "51") (name "Net-(LED4-PadA)") (class "Default")
      (node (ref "LED4") (pin "A") (pinfunction "A_A") (pintype "passive"))
      (node (ref "RL4") (pin "2") (pinfunction "2_2") (pintype "passive"))
    )
    (net (code "52") (name "Net-(LED9-PadA)") (class "Default")
      (node (ref "LED9") (pin "A") (pinfunction "A_A") (pintype "passive"))
      (node (ref "R12") (pin "1") (pinfunction "1_1") (pintype "passive"))
    )
    (net (code "53") (name "Net-(LED10-PadA)") (class "Default")
      (node (ref "LED10") (pin "A") (pinfunction "A_A") (pintype "passive"))
      (node (ref "RL3") (pin "1") (pinfunction "1_1") (pintype "passive"))
    )
    (net (code "54") (name "Net-(LED11-PadA)") (class "Default")
      (node (ref "LED11") (pin "A") (pinfunction "A_A") (pintype "passive"))
      (node (ref "R14") (pin "1") (pinfunction "1_1") (pintype "passive"))
    )
    (net (code "55") (name "Net-(LED11-PadC)") (class "Default")
      (node (ref "LED11") (pin "C") (pinfunction "C_C") (pintype "passive"))
      (node (ref "U$3") (pin "NET") (pinfunction "NET_NET") (pintype "bidirectional"))
    )
    (net (code "56") (name "Net-(LED12-PadA)") (class "Default")
      (node (ref "LED12") (pin "A") (pinfunction "A_A") (pintype "passive"))
      (node (ref "R39") (pin "1") (pinfunction "1_1") (pintype "passive"))
    )
    (net (code "57") (name "Net-(LED12-PadC)") (class "Default")
      (node (ref "LED12") (pin "C") (pinfunction "C_C") (pintype "passive"))
      (node (ref "U$3") (pin "ALM") (pinfunction "ALM_ALM") (pintype "bidirectional"))
    )
    (net (code "58") (name "Net-(LED18-PadA)") (class "Default")
      (node (ref "LED18") (pin "A") (pinfunction "A_A") (pintype "passive"))
      (node (ref "RL1") (pin "2") (pinfunction "2_2") (pintype "passive"))
    )
    (net (code "59") (name "Net-(LED19-PadA)") (class "Default")
      (node (ref "LED19") (pin "A") (pinfunction "A_A") (pintype "passive"))
      (node (ref "RL7") (pin "2") (pinfunction "2_2") (pintype "passive"))
    )
    (net (code "60") (name "Net-(R8-Pad2)") (class "Default")
      (node (ref "R8") (pin "2") (pinfunction "2_2") (pintype "passive"))
      (node (ref "U$3") (pin "TX1") (pinfunction "TX1_TX1") (pintype "bidirectional"))
    )
    (net (code "61") (name "Net-(R11-Pad2)") (class "Default")
      (node (ref "R11") (pin "2") (pinfunction "2_2") (pintype "passive"))
      (node (ref "U$3") (pin "RX1") (pinfunction "RX1_RX1") (pintype "bidirectional"))
    )
    (net (code "62") (name "Net-(R24-Pad2)") (class "Default")
      (node (ref "R24") (pin "2") (pinfunction "2_2") (pintype "passive"))
      (node (ref "X4") (pin "3") (pinfunction "3_3") (pintype "passive"))
    )
    (net (code "63") (name "Net-(R31-Pad2)") (class "Default")
      (node (ref "R31") (pin "2") (pinfunction "2_2") (pintype "passive"))
      (node (ref "X4") (pin "2") (pinfunction "2_2") (pintype "passive"))
    )
    (net (code "64") (name "Net-(RGB-J1-2)") (class "Default")
      (node (ref "Q8") (pin "2") (pinfunction "D_2") (pintype "passive"))
      (node (ref "RGB-J1") (pin "R") (pinfunction "2_R") (pintype "bidirectional"))
    )
    (net (code "65") (name "Net-(RGB-J1-3)") (class "Default")
      (node (ref "Q9") (pin "2") (pinfunction "D_2") (pintype "passive"))
      (node (ref "RGB-J1") (pin "B") (pinfunction "3_B") (pintype "bidirectional"))
    )
    (net (code "66") (name "Net-(RGB-J1-4)") (class "Default")
      (node (ref "Q10") (pin "2") (pinfunction "D_2") (pintype "passive"))
      (node (ref "RGB-J1") (pin "G") (pinfunction "4_G") (pintype "bidirectional"))
    )
    (net (code "67") (name "Net-(RGB-J2-2)") (class "Default")
      (node (ref "Q7") (pin "2") (pinfunction "D_2") (pintype "passive"))
      (node (ref "RGB-J2") (pin "R") (pinfunction "2_R") (pintype "bidirectional"))
    )
    (net (code "68") (name "Net-(RGB-J2-3)") (class "Default")
      (node (ref "Q11") (pin "2") (pinfunction "D_2") (pintype "passive"))
      (node (ref "RGB-J2") (pin "B") (pinfunction "3_B") (pintype "bidirectional"))
    )
    (net (code "69") (name "Net-(RGB-J2-4)") (class "Default")
      (node (ref "Q12") (pin "2") (pinfunction "D_2") (pintype "passive"))
      (node (ref "RGB-J2") (pin "G") (pinfunction "4_G") (pintype "bidirectional"))
    )
    (net (code "70") (name "Net-(U$1-DACL)") (class "Default")
      (node (ref "U$1") (pin "5") (pinfunction "DACL_5") (pintype "output"))
      (node (ref "X1") (pin "2") (pinfunction "2_2") (pintype "passive"))
    )
    (net (code "71") (name "Net-(U$1-DACR)") (class "Default")
      (node (ref "U$1") (pin "4") (pinfunction "DACR_4") (pintype "output"))
      (node (ref "X1") (pin "3") (pinfunction "3_3") (pintype "passive"))
    )
    (net (code "72") (name "Net-(U$1-RX)") (class "Default")
      (node (ref "R1") (pin "1") (pinfunction "1_1") (pintype "passive"))
      (node (ref "U$1") (pin "2") (pinfunction "RX_2") (pintype "input"))
    )
    (net (code "73") (name "Net-(U$1-TX)") (class "Default")
      (node (ref "R2") (pin "1") (pinfunction "1_1") (pintype "passive"))
      (node (ref "U$1") (pin "3") (pinfunction "TX_3") (pintype "output"))
    )
    (net (code "74") (name "Net-(U$3-RNU)") (class "Default")
      (node (ref "LED9") (pin "C") (pinfunction "C_C") (pintype "passive"))
      (node (ref "U$3") (pin "RUN") (pinfunction "RNU_RUN") (pintype "bidirectional"))
    )
    (net (code "75") (name "Net-(U$4-UCAP)") (class "Default")
      (node (ref "C3") (pin "2") (pinfunction "2_2") (pintype "passive"))
      (node (ref "U$4") (pin "6") (pinfunction "UCAP_6") (pintype "bidirectional"))
    )
    (net (code "76") (name "VUSB") (class "Default")
      (node (ref "C7") (pin "2") (pinfunction "2_2") (pintype "passive"))
      (node (ref "D4") (pin "A") (pinfunction "A_A") (pintype "passive"))
      (node (ref "U$4") (pin "7") (pinfunction "VBUS_7") (pintype "bidirectional"))
      (node (ref "X4") (pin "1") (pinfunction "1_1") (pintype "passive"))
    )
    (net (code "77") (name "unconnected-(CFG-Pad2)") (class "Default")
      (node (ref "CFG") (pin "2") (pinfunction "2_2") (pintype "passive"))
    )
    (net (code "78") (name "unconnected-(CFG-Pad3)") (class "Default")
      (node (ref "CFG") (pin "3") (pinfunction "3_3") (pintype "passive"))
    )
    (net (code "79") (name "unconnected-(Q1-D-Pad4)") (class "Default")
      (node (ref "Q1") (pin "4") (pinfunction "D_4") (pintype "passive"))
    )
    (net (code "80") (name "unconnected-(Q2-D-Pad4)") (class "Default")
      (node (ref "Q2") (pin "4") (pinfunction "D_4") (pintype "passive"))
    )
    (net (code "81") (name "unconnected-(Q4-D-Pad4)") (class "Default")
      (node (ref "Q4") (pin "4") (pinfunction "D_4") (pintype "passive"))
    )
    (net (code "82") (name "unconnected-(Q5-D-Pad4)") (class "Default")
      (node (ref "Q5") (pin "4") (pinfunction "D_4") (pintype "passive"))
    )
    (net (code "83") (name "unconnected-(Q6-D-Pad4)") (class "Default")
      (node (ref "Q6") (pin "4") (pinfunction "D_4") (pintype "passive"))
    )
    (net (code "84") (name "unconnected-(Q7-D-Pad4)") (class "Default")
      (node (ref "Q7") (pin "4") (pinfunction "D_4") (pintype "passive"))
    )
    (net (code "85") (name "unconnected-(Q8-D-Pad4)") (class "Default")
      (node (ref "Q8") (pin "4") (pinfunction "D_4") (pintype "passive"))
    )
    (net (code "86") (name "unconnected-(Q9-D-Pad4)") (class "Default")
      (node (ref "Q9") (pin "4") (pinfunction "D_4") (pintype "passive"))
    )
    (net (code "87") (name "unconnected-(Q10-D-Pad4)") (class "Default")
      (node (ref "Q10") (pin "4") (pinfunction "D_4") (pintype "passive"))
    )
    (net (code "88") (name "unconnected-(Q11-D-Pad4)") (class "Default")
      (node (ref "Q11") (pin "4") (pinfunction "D_4") (pintype "passive"))
    )
    (net (code "89") (name "unconnected-(Q12-D-Pad4)") (class "Default")
      (node (ref "Q12") (pin "4") (pinfunction "D_4") (pintype "passive"))
    )
    (net (code "90") (name "unconnected-(RESET1-Pad1)") (class "Default")
      (node (ref "RESET1") (pin "1") (pinfunction "1_1") (pintype "passive"))
    )
    (net (code "91") (name "unconnected-(RESET1-Pad3)") (class "Default")
      (node (ref "RESET1") (pin "3") (pinfunction "3_3") (pintype "passive"))
    )
    (net (code "92") (name "unconnected-(U$1-BUSY-Pad16)") (class "Default")
      (node (ref "U$1") (pin "16") (pinfunction "BUSY_16") (pintype "output"))
    )
    (net (code "93") (name "unconnected-(U$1-IO1-Pad9)") (class "Default")
      (node (ref "U$1") (pin "9") (pinfunction "IO1_9") (pintype "bidirectional"))
    )
    (net (code "94") (name "unconnected-(U$1-IO2-Pad11)") (class "Default")
      (node (ref "U$1") (pin "11") (pinfunction "IO2_11") (pintype "bidirectional"))
    )
    (net (code "95") (name "unconnected-(U$1-KEY1-Pad12)") (class "Default")
      (node (ref "U$1") (pin "12") (pinfunction "KEY1_12") (pintype "input"))
    )
    (net (code "96") (name "unconnected-(U$1-KEY2-Pad13)") (class "Default")
      (node (ref "U$1") (pin "13") (pinfunction "KEY2_13") (pintype "input"))
    )
    (net (code "97") (name "unconnected-(U$1-SPK1-Pad6)") (class "Default")
      (node (ref "U$1") (pin "6") (pinfunction "SPK1_6") (pintype "output"))
    )
    (net (code "98") (name "unconnected-(U$1-SPK2-Pad8)") (class "Default")
      (node (ref "U$1") (pin "8") (pinfunction "SPK2_8") (pintype "output"))
    )
    (net (code "99") (name "unconnected-(U$1-USB+-Pad14)") (class "Default")
      (node (ref "U$1") (pin "14") (pinfunction "USB+_14") (pintype "bidirectional"))
    )
    (net (code "100") (name "unconnected-(U$1-USB--Pad15)") (class "Default")
      (node (ref "U$1") (pin "15") (pinfunction "USB-_15") (pintype "bidirectional"))
    )
    (net (code "101") (name "unconnected-(U$3-PadRST)") (class "Default")
      (node (ref "U$3") (pin "RST") (pinfunction "RST_RST") (pintype "bidirectional"))
    )
    (net (code "102") (name "unconnected-(X1-Pad4)") (class "Default")
      (node (ref "X1") (pin "4") (pinfunction "4_4") (pintype "passive"))
    )
    (net (code "103") (name "unconnected-(X1-Pad5)") (class "Default")
      (node (ref "X1") (pin "5") (pinfunction "5_5") (pintype "passive"))
    )
    (net (code "104") (name "unconnected-(X4-Pad4)") (class "Default")
      (node (ref "X4") (pin "4") (pinfunction "4_4") (pintype "passive"))
    )
  )
)
